# led8pins.net
KiCad netlist of a schematic drawn in EAGLE
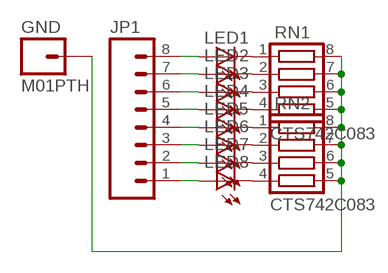
[diagram p0: schematic, sheet 1]

(export (version "E")
  (design (tool "Eeschema 10.0.6"))
  (components
    (comp (ref "GND")
      (value "M01PTH")
      (footprint "eagle-import:1X01")
      (libsource (lib "eagle-import") (part "M01PTH"))
    )
    (comp (ref "JP1")
      (value "M081X08")
      (footprint "eagle-import:1X08")
      (libsource (lib "eagle-import") (part "M081X08"))
    )
    (comp (ref "LED1")
      (value "LEDCHIP-LED0603")
      (footprint "eagle-import:CHIP-LED0603")
      (libsource (lib "eagle-import") (part "LEDCHIP-LED0603"))
    )
    (comp (ref "LED2")
      (value "LEDCHIP-LED0603")
      (footprint "eagle-import:CHIP-LED0603")
      (libsource (lib "eagle-import") (part "LEDCHIP-LED0603"))
    )
    (comp (ref "LED3")
      (value "LEDCHIP-LED0603")
      (footprint "eagle-import:CHIP-LED0603")
      (libsource (lib "eagle-import") (part "LEDCHIP-LED0603"))
    )
    (comp (ref "LED4")
      (value "LEDCHIP-LED0603")
      (footprint "eagle-import:CHIP-LED0603")
      (libsource (lib "eagle-import") (part "LEDCHIP-LED0603"))
    )
    (comp (ref "LED5")
      (value "LEDCHIP-LED0603")
      (footprint "eagle-import:CHIP-LED0603")
      (libsource (lib "eagle-import") (part "LEDCHIP-LED0603"))
    )
    (comp (ref "LED6")
      (value "LEDCHIP-LED0603")
      (footprint "eagle-import:CHIP-LED0603")
      (libsource (lib "eagle-import") (part "LEDCHIP-LED0603"))
    )
    (comp (ref "LED7")
      (value "LEDCHIP-LED0603")
      (footprint "eagle-import:CHIP-LED0603")
      (libsource (lib "eagle-import") (part "LEDCHIP-LED0603"))
    )
    (comp (ref "LED8")
      (value "LEDCHIP-LED0603")
      (footprint "eagle-import:CHIP-LED0603")
      (libsource (lib "eagle-import") (part "LEDCHIP-LED0603"))
    )
    (comp (ref "RN1")
      (value "CTS742C083")
      (footprint "eagle-import:CTS742C083")
      (libsource (lib "eagle-import") (part "CTS742C083"))
    )
    (comp (ref "RN2")
      (value "CTS742C083")
      (footprint "eagle-import:CTS742C083")
      (libsource (lib "eagle-import") (part "CTS742C083"))
    )
  )
  (nets
    (net (code "1") (name "Net-(GND-Pad1)") (class "Default")
      (node (ref "GND") (pin "1") (pinfunction "1_1") (pintype "passive"))
      (node (ref "RN1") (pin "5") (pinfunction "5_5") (pintype "passive"))
      (node (ref "RN1") (pin "6") (pinfunction "6_6") (pintype "passive"))
      (node (ref "RN1") (pin "7") (pinfunction "7_7") (pintype "passive"))
      (node (ref "RN1") (pin "8") (pinfunction "8_8") (pintype "passive"))
      (node (ref "RN2") (pin "5") (pinfunction "5_5") (pintype "passive"))
      (node (ref "RN2") (pin "6") (pinfunction "6_6") (pintype "passive"))
      (node (ref "RN2") (pin "7") (pinfunction "7_7") (pintype "passive"))
      (node (ref "RN2") (pin "8") (pinfunction "8_8") (pintype "passive"))
    )
    (net (code "2") (name "Net-(JP1-Pad1)") (class "Default")
      (node (ref "JP1") (pin "1") (pinfunction "1_1") (pintype "passive"))
      (node (ref "LED8") (pin "A") (pinfunction "A_A") (pintype "passive"))
    )
    (net (code "3") (name "Net-(JP1-Pad2)") (class "Default")
      (node (ref "JP1") (pin "2") (pinfunction "2_2") (pintype "passive"))
      (node (ref "LED7") (pin "A") (pinfunction "A_A") (pintype "passive"))
    )
    (net (code "4") (name "Net-(JP1-Pad3)") (class "Default")
      (node (ref "JP1") (pin "3") (pinfunction "3_3") (pintype "passive"))
      (node (ref "LED6") (pin "A") (pinfunction "A_A") (pintype "passive"))
    )
    (net (code "5") (name "Net-(JP1-Pad4)") (class "Default")
      (node (ref "JP1") (pin "4") (pinfunction "4_4") (pintype "passive"))
      (node (ref "LED5") (pin "A") (pinfunction "A_A") (pintype "passive"))
    )
    (net (code "6") (name "Net-(JP1-Pad5)") (class "Default")
      (node (ref "JP1") (pin "5") (pinfunction "5_5") (pintype "passive"))
      (node (ref "LED4") (pin "A") (pinfunction "A_A") (pintype "passive"))
    )
    (net (code "7") (name "Net-(JP1-Pad6)") (class "Default")
      (node (ref "JP1") (pin "6") (pinfunction "6_6") (pintype "passive"))
      (node (ref "LED3") (pin "A") (pinfunction "A_A") (pintype "passive"))
    )
    (net (code "8") (name "Net-(JP1-Pad7)") (class "Default")
      (node (ref "JP1") (pin "7") (pinfunction "7_7") (pintype "passive"))
      (node (ref "LED2") (pin "A") (pinfunction "A_A") (pintype "passive"))
    )
    (net (code "9") (name "Net-(JP1-Pad8)") (class "Default")
      (node (ref "JP1") (pin "8") (pinfunction "8_8") (pintype "passive"))
      (node (ref "LED1") (pin "A") (pinfunction "A_A") (pintype "passive"))
    )
    (net (code "10") (name "Net-(LED1-PadC)") (class "Default")
      (node (ref "LED1") (pin "C") (pinfunction "C_C") (pintype "passive"))
      (node (ref "RN1") (pin "1") (pinfunction "1_1") (pintype "passive"))
    )
    (net (code "11") (name "Net-(LED2-PadC)") (class "Default")
      (node (ref "LED2") (pin "C") (pinfunction "C_C") (pintype "passive"))
      (node (ref "RN1") (pin "2") (pinfunction "2_2") (pintype "passive"))
    )
    (net (code "12") (name "Net-(LED3-PadC)") (class "Default")
      (node (ref "LED3") (pin "C") (pinfunction "C_C") (pintype "passive"))
      (node (ref "RN1") (pin "3") (pinfunction "3_3") (pintype "passive"))
    )
    (net (code "13") (name "Net-(LED4-PadC)") (class "Default")
      (node (ref "LED4") (pin "C") (pinfunction "C_C") (pintype "passive"))
      (node (ref "RN1") (pin "4") (pinfunction "4_4") (pintype "passive"))
    )
    (net (code "14") (name "Net-(LED5-PadC)") (class "Default")
      (node (ref "LED5") (pin "C") (pinfunction "C_C") (pintype "passive"))
      (node (ref "RN2") (pin "1") (pinfunction "1_1") (pintype "passive"))
    )
    (net (code "15") (name "Net-(LED6-PadC)") (class "Default")
      (node (ref "LED6") (pin "C") (pinfunction "C_C") (pintype "passive"))
      (node (ref "RN2") (pin "2") (pinfunction "2_2") (pintype "passive"))
    )
    (net (code "16") (name "Net-(LED7-PadC)") (class "Default")
      (node (ref "LED7") (pin "C") (pinfunction "C_C") (pintype "passive"))
      (node (ref "RN2") (pin "3") (pinfunction "3_3") (pintype "passive"))
    )
    (net (code "17") (name "Net-(LED8-PadC)") (class "Default")
      (node (ref "LED8") (pin "C") (pinfunction "C_C") (pintype "passive"))
      (node (ref "RN2") (pin "4") (pinfunction "4_4") (pintype "passive"))
    )
  )
)
